# minicar_r3.net
KiCad netlist of a schematic drawn in EAGLE
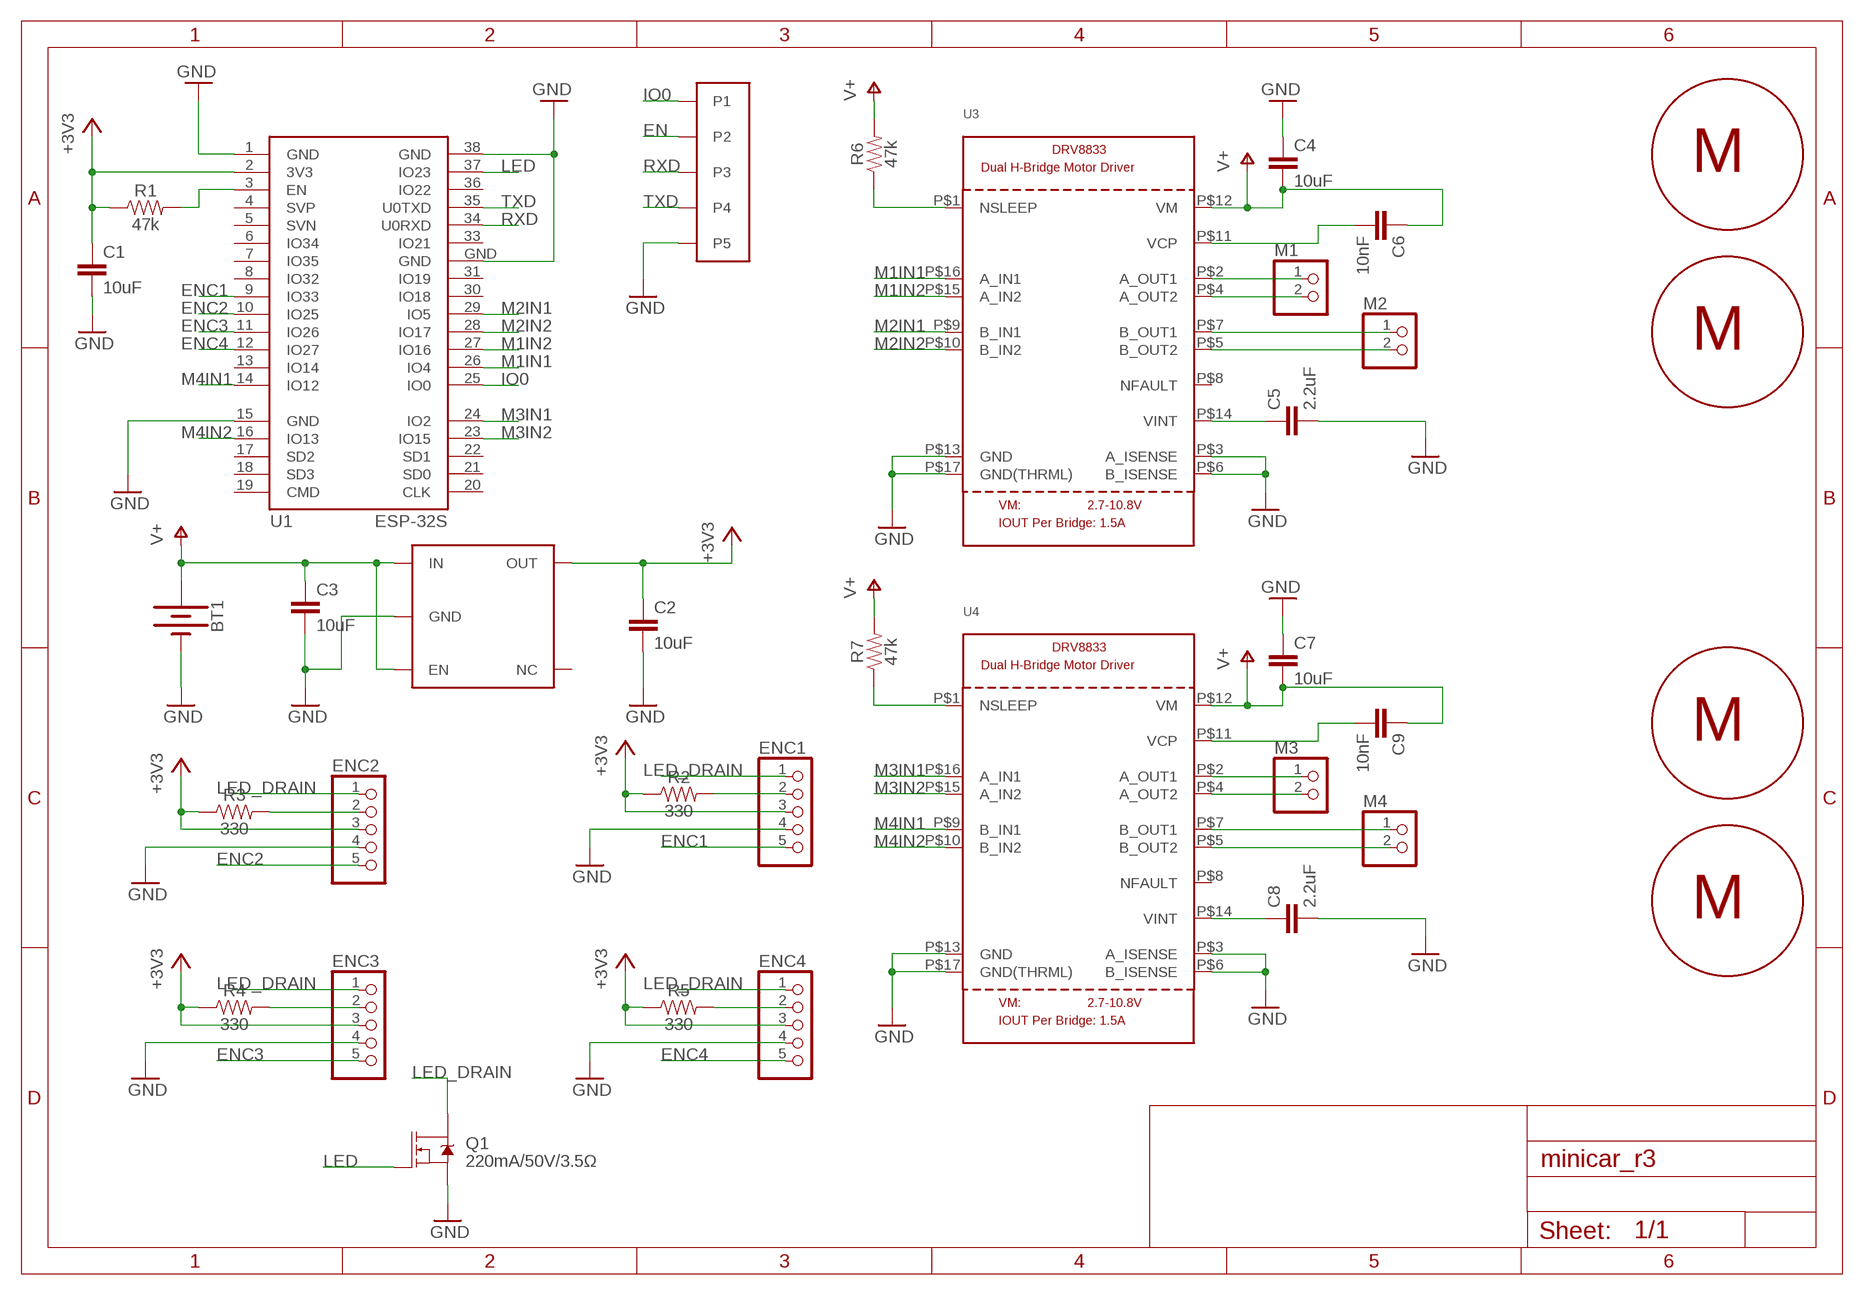
[diagram p0: schematic, sheet 1]

(export (version "E")
  (design (tool "Eeschema 10.0.6"))
  (components
    (comp (ref "BT1")
      (value "BATTERY-AA")
      (footprint "eagle-import:BATTERY-AA")
      (libsource (lib "eagle-import") (part "BATTERY-AA"))
    )
    (comp (ref "C1")
      (value "10uF")
      (footprint "eagle-import:0805")
      (libsource (lib "eagle-import") (part "10UF-0805-10V-10%"))
    )
    (comp (ref "C2")
      (value "10uF")
      (footprint "eagle-import:0805")
      (libsource (lib "eagle-import") (part "10UF-0805-10V-10%"))
    )
    (comp (ref "C3")
      (value "10uF")
      (footprint "eagle-import:0805")
      (libsource (lib "eagle-import") (part "10UF-0805-10V-10%"))
    )
    (comp (ref "C4")
      (value "10uF")
      (footprint "eagle-import:0805")
      (libsource (lib "eagle-import") (part "10UF-0805-10V-10%"))
    )
    (comp (ref "C5")
      (value "2.2uF")
      (footprint "eagle-import:0603")
      (libsource (lib "eagle-import") (part "2.2UF-0603-10V-20%"))
    )
    (comp (ref "C6")
      (value "10nF")
      (footprint "eagle-import:0603")
      (libsource (lib "eagle-import") (part "10NF-0603-50V-10%"))
    )
    (comp (ref "C7")
      (value "10uF")
      (footprint "eagle-import:0805")
      (libsource (lib "eagle-import") (part "10UF-0805-10V-10%"))
    )
    (comp (ref "C8")
      (value "2.2uF")
      (footprint "eagle-import:0603")
      (libsource (lib "eagle-import") (part "2.2UF-0603-10V-20%"))
    )
    (comp (ref "C9")
      (value "10nF")
      (footprint "eagle-import:0603")
      (libsource (lib "eagle-import") (part "10NF-0603-50V-10%"))
    )
    (comp (ref "ENC1")
      (value "PINHD-1X5")
      (footprint "eagle-import:1X05")
      (libsource (lib "eagle-import") (part "PINHD-1X5"))
    )
    (comp (ref "ENC2")
      (value "PINHD-1X5")
      (footprint "eagle-import:1X05")
      (libsource (lib "eagle-import") (part "PINHD-1X5"))
    )
    (comp (ref "ENC3")
      (value "PINHD-1X5")
      (footprint "eagle-import:1X05")
      (libsource (lib "eagle-import") (part "PINHD-1X5"))
    )
    (comp (ref "ENC4")
      (value "PINHD-1X5")
      (footprint "eagle-import:1X05")
      (libsource (lib "eagle-import") (part "PINHD-1X5"))
    )
    (comp (ref "M1")
      (value "PINHD-1X2")
      (footprint "eagle-import:1X02")
      (libsource (lib "eagle-import") (part "PINHD-1X2"))
    )
    (comp (ref "M2")
      (value "PINHD-1X2")
      (footprint "eagle-import:1X02")
      (libsource (lib "eagle-import") (part "PINHD-1X2"))
    )
    (comp (ref "M3")
      (value "PINHD-1X2")
      (footprint "eagle-import:1X02")
      (libsource (lib "eagle-import") (part "PINHD-1X2"))
    )
    (comp (ref "M4")
      (value "PINHD-1X2")
      (footprint "eagle-import:1X02")
      (libsource (lib "eagle-import") (part "PINHD-1X2"))
    )
    (comp (ref "Q1")
      (value "220mA/50V/3.5Ω")
      (footprint "eagle-import:SOT23-3")
      (libsource (lib "eagle-import") (part "MOSFET-NCH-BSS138"))
    )
    (comp (ref "R1")
      (value "47k")
      (footprint "eagle-import:0603")
      (libsource (lib "eagle-import") (part "47KOHM-0603-1/10W-1%"))
    )
    (comp (ref "R2")
      (value "330")
      (footprint "eagle-import:0603")
      (libsource (lib "eagle-import") (part "330OHM-0603-1/10W-1%"))
    )
    (comp (ref "R3")
      (value "330")
      (footprint "eagle-import:0603")
      (libsource (lib "eagle-import") (part "330OHM-0603-1/10W-1%"))
    )
    (comp (ref "R4")
      (value "330")
      (footprint "eagle-import:0603")
      (libsource (lib "eagle-import") (part "330OHM-0603-1/10W-1%"))
    )
    (comp (ref "R5")
      (value "330")
      (footprint "eagle-import:0603")
      (libsource (lib "eagle-import") (part "330OHM-0603-1/10W-1%"))
    )
    (comp (ref "R6")
      (value "47k")
      (footprint "eagle-import:0603")
      (libsource (lib "eagle-import") (part "47KOHM-0603-1/10W-1%"))
    )
    (comp (ref "R7")
      (value "47k")
      (footprint "eagle-import:0603")
      (libsource (lib "eagle-import") (part "47KOHM-0603-1/10W-1%"))
    )
    (comp (ref "U$2")
      (value "MOTOR_10X27MM")
      (footprint "eagle-import:MOTOR")
      (libsource (lib "eagle-import") (part "MOTOR_10X27MM"))
    )
    (comp (ref "U$3")
      (value "MOTOR_10X27MM")
      (footprint "eagle-import:MOTOR")
      (libsource (lib "eagle-import") (part "MOTOR_10X27MM"))
    )
    (comp (ref "U$4")
      (value "MOTOR_10X27MM")
      (footprint "eagle-import:MOTOR")
      (libsource (lib "eagle-import") (part "MOTOR_10X27MM"))
    )
    (comp (ref "U$5")
      (value "MOTOR_10X27MM")
      (footprint "eagle-import:MOTOR")
      (libsource (lib "eagle-import") (part "MOTOR_10X27MM"))
    )
    (comp (ref "U1")
      (value "ESP-32S")
      (footprint "eagle-import:ESP-32S")
      (libsource (lib "eagle-import") (part "ESP-32S"))
    )
    (comp (ref "U2")
      (value "53047")
      (footprint "eagle-import:PICOBLADE_53047")
      (libsource (lib "eagle-import") (part "53047"))
    )
    (comp (ref "U3")
      (value "DRV8833")
      (footprint "eagle-import:HTSSOP16")
      (libsource (lib "eagle-import") (part "DRV8833"))
    )
    (comp (ref "U4")
      (value "DRV8833")
      (footprint "eagle-import:HTSSOP16")
      (libsource (lib "eagle-import") (part "DRV8833"))
    )
    (comp (ref "U5")
      (value "TLV755")
      (footprint "eagle-import:SOT23-DBV")
      (libsource (lib "eagle-import") (part "TLV755"))
    )
  )
  (nets
    (net (code "1") (name "+3V3") (class "Default")
      (node (ref "C1") (pin "1") (pinfunction "1_1") (pintype "passive"))
      (node (ref "C2") (pin "1") (pinfunction "1_1") (pintype "passive"))
      (node (ref "ENC1") (pin "3") (pinfunction "3_3") (pintype "passive"))
      (node (ref "ENC2") (pin "3") (pinfunction "3_3") (pintype "passive"))
      (node (ref "ENC3") (pin "3") (pinfunction "3_3") (pintype "passive"))
      (node (ref "ENC4") (pin "3") (pinfunction "3_3") (pintype "passive"))
      (node (ref "R1") (pin "1") (pinfunction "1_1") (pintype "passive"))
      (node (ref "R2") (pin "1") (pinfunction "1_1") (pintype "passive"))
      (node (ref "R3") (pin "1") (pinfunction "1_1") (pintype "passive"))
      (node (ref "R4") (pin "1") (pinfunction "1_1") (pintype "passive"))
      (node (ref "R5") (pin "1") (pinfunction "1_1") (pintype "passive"))
      (node (ref "U1") (pin "2") (pinfunction "3V3_2") (pintype "power_in"))
      (node (ref "U5") (pin "5") (pinfunction "OUT_5") (pintype "bidirectional"))
    )
    (net (code "2") (name "/EN") (class "Default")
      (node (ref "R1") (pin "2") (pinfunction "2_2") (pintype "passive"))
      (node (ref "U1") (pin "3") (pinfunction "EN_3") (pintype "input"))
      (node (ref "U2") (pin "P$2") (pinfunction "P2_P$2") (pintype "bidirectional"))
    )
    (net (code "3") (name "/ENC1") (class "Default")
      (node (ref "ENC1") (pin "5") (pinfunction "5_5") (pintype "passive"))
      (node (ref "U1") (pin "9") (pinfunction "IO33_9") (pintype "bidirectional"))
    )
    (net (code "4") (name "/ENC2") (class "Default")
      (node (ref "ENC2") (pin "5") (pinfunction "5_5") (pintype "passive"))
      (node (ref "U1") (pin "10") (pinfunction "IO25_10") (pintype "bidirectional"))
    )
    (net (code "5") (name "/ENC3") (class "Default")
      (node (ref "ENC3") (pin "5") (pinfunction "5_5") (pintype "passive"))
      (node (ref "U1") (pin "11") (pinfunction "IO26_11") (pintype "bidirectional"))
    )
    (net (code "6") (name "/ENC4") (class "Default")
      (node (ref "ENC4") (pin "5") (pinfunction "5_5") (pintype "passive"))
      (node (ref "U1") (pin "12") (pinfunction "IO27_12") (pintype "bidirectional"))
    )
    (net (code "7") (name "/IO0") (class "Default")
      (node (ref "U1") (pin "25") (pinfunction "IO0_25") (pintype "bidirectional"))
      (node (ref "U2") (pin "P$1") (pinfunction "P1_P$1") (pintype "bidirectional"))
    )
    (net (code "8") (name "/LED") (class "Default")
      (node (ref "Q1") (pin "1") (pinfunction "G_1") (pintype "bidirectional"))
      (node (ref "U1") (pin "37") (pinfunction "IO23_37") (pintype "bidirectional"))
    )
    (net (code "9") (name "/LED_DRAIN") (class "Default")
      (node (ref "ENC1") (pin "1") (pinfunction "1_1") (pintype "passive"))
      (node (ref "ENC2") (pin "1") (pinfunction "1_1") (pintype "passive"))
      (node (ref "ENC3") (pin "1") (pinfunction "1_1") (pintype "passive"))
      (node (ref "ENC4") (pin "1") (pinfunction "1_1") (pintype "passive"))
      (node (ref "Q1") (pin "3") (pinfunction "D_3") (pintype "bidirectional"))
    )
    (net (code "10") (name "/M1IN1") (class "Default")
      (node (ref "U1") (pin "26") (pinfunction "IO4_26") (pintype "bidirectional"))
      (node (ref "U3") (pin "P$16") (pinfunction "A_IN1_P$16") (pintype "input"))
    )
    (net (code "11") (name "/M1IN2") (class "Default")
      (node (ref "U1") (pin "27") (pinfunction "IO16_27") (pintype "bidirectional"))
      (node (ref "U3") (pin "P$15") (pinfunction "A_IN2_P$15") (pintype "input"))
    )
    (net (code "12") (name "/M2IN1") (class "Default")
      (node (ref "U1") (pin "29") (pinfunction "IO5_29") (pintype "bidirectional"))
      (node (ref "U3") (pin "P$9") (pinfunction "B_IN1_P$9") (pintype "input"))
    )
    (net (code "13") (name "/M2IN2") (class "Default")
      (node (ref "U1") (pin "28") (pinfunction "IO17_28") (pintype "bidirectional"))
      (node (ref "U3") (pin "P$10") (pinfunction "B_IN2_P$10") (pintype "input"))
    )
    (net (code "14") (name "/M3IN1") (class "Default")
      (node (ref "U1") (pin "24") (pinfunction "IO2_24") (pintype "bidirectional"))
      (node (ref "U4") (pin "P$16") (pinfunction "A_IN1_P$16") (pintype "input"))
    )
    (net (code "15") (name "/M3IN2") (class "Default")
      (node (ref "U1") (pin "23") (pinfunction "IO15_23") (pintype "bidirectional"))
      (node (ref "U4") (pin "P$15") (pinfunction "A_IN2_P$15") (pintype "input"))
    )
    (net (code "16") (name "/M4IN1") (class "Default")
      (node (ref "U1") (pin "14") (pinfunction "IO12_14") (pintype "bidirectional"))
      (node (ref "U4") (pin "P$9") (pinfunction "B_IN1_P$9") (pintype "input"))
    )
    (net (code "17") (name "/M4IN2") (class "Default")
      (node (ref "U1") (pin "16") (pinfunction "IO13_16") (pintype "bidirectional"))
      (node (ref "U4") (pin "P$10") (pinfunction "B_IN2_P$10") (pintype "input"))
    )
    (net (code "18") (name "/RXD") (class "Default")
      (node (ref "U1") (pin "34") (pinfunction "U0RXD_34") (pintype "bidirectional"))
      (node (ref "U2") (pin "P$3") (pinfunction "P3_P$3") (pintype "bidirectional"))
    )
    (net (code "19") (name "/TXD") (class "Default")
      (node (ref "U1") (pin "35") (pinfunction "U0TXD_35") (pintype "bidirectional"))
      (node (ref "U2") (pin "P$4") (pinfunction "P4_P$4") (pintype "bidirectional"))
    )
    (net (code "20") (name "GND") (class "Default")
      (node (ref "BT1") (pin "GND@1") (pinfunction "-_GND@1") (pintype "power_in"))
      (node (ref "C1") (pin "2") (pinfunction "2_2") (pintype "passive"))
      (node (ref "C2") (pin "2") (pinfunction "2_2") (pintype "passive"))
      (node (ref "C3") (pin "2") (pinfunction "2_2") (pintype "passive"))
      (node (ref "C4") (pin "1") (pinfunction "1_1") (pintype "passive"))
      (node (ref "C5") (pin "2") (pinfunction "2_2") (pintype "passive"))
      (node (ref "C7") (pin "1") (pinfunction "1_1") (pintype "passive"))
      (node (ref "C8") (pin "2") (pinfunction "2_2") (pintype "passive"))
      (node (ref "ENC1") (pin "4") (pinfunction "4_4") (pintype "passive"))
      (node (ref "ENC2") (pin "4") (pinfunction "4_4") (pintype "passive"))
      (node (ref "ENC3") (pin "4") (pinfunction "4_4") (pintype "passive"))
      (node (ref "ENC4") (pin "4") (pinfunction "4_4") (pintype "passive"))
      (node (ref "Q1") (pin "2") (pinfunction "S_2") (pintype "bidirectional"))
      (node (ref "U1") (pin "1") (pinfunction "GND_1") (pintype "power_in"))
      (node (ref "U1") (pin "15") (pinfunction "GND_15") (pintype "power_in"))
      (node (ref "U1") (pin "38") (pinfunction "GND_38") (pintype "power_in"))
      (node (ref "U1") (pin "GND") (pinfunction "GND_GND") (pintype "power_in"))
      (node (ref "U2") (pin "P$5") (pinfunction "P5_P$5") (pintype "bidirectional"))
      (node (ref "U3") (pin "P$13") (pinfunction "GND_P$13") (pintype "power_in"))
      (node (ref "U3") (pin "P$17") (pinfunction "GND(THRML)_P$17") (pintype "power_in"))
      (node (ref "U3") (pin "P$3") (pinfunction "A_ISENSE_P$3") (pintype "bidirectional"))
      (node (ref "U3") (pin "P$6") (pinfunction "B_ISENSE_P$6") (pintype "bidirectional"))
      (node (ref "U4") (pin "P$13") (pinfunction "GND_P$13") (pintype "power_in"))
      (node (ref "U4") (pin "P$17") (pinfunction "GND(THRML)_P$17") (pintype "power_in"))
      (node (ref "U4") (pin "P$3") (pinfunction "A_ISENSE_P$3") (pintype "bidirectional"))
      (node (ref "U4") (pin "P$6") (pinfunction "B_ISENSE_P$6") (pintype "bidirectional"))
      (node (ref "U5") (pin "2") (pinfunction "GND_2") (pintype "bidirectional"))
    )
    (net (code "21") (name "Net-(ENC1-Pad2)") (class "Default")
      (node (ref "ENC1") (pin "2") (pinfunction "2_2") (pintype "passive"))
      (node (ref "R2") (pin "2") (pinfunction "2_2") (pintype "passive"))
    )
    (net (code "22") (name "Net-(ENC2-Pad2)") (class "Default")
      (node (ref "ENC2") (pin "2") (pinfunction "2_2") (pintype "passive"))
      (node (ref "R3") (pin "2") (pinfunction "2_2") (pintype "passive"))
    )
    (net (code "23") (name "Net-(ENC3-Pad2)") (class "Default")
      (node (ref "ENC3") (pin "2") (pinfunction "2_2") (pintype "passive"))
      (node (ref "R4") (pin "2") (pinfunction "2_2") (pintype "passive"))
    )
    (net (code "24") (name "Net-(ENC4-Pad2)") (class "Default")
      (node (ref "ENC4") (pin "2") (pinfunction "2_2") (pintype "passive"))
      (node (ref "R5") (pin "2") (pinfunction "2_2") (pintype "passive"))
    )
    (net (code "25") (name "Net-(U3-A_OUT1)") (class "Default")
      (node (ref "M1") (pin "1") (pinfunction "1_1") (pintype "passive"))
      (node (ref "U3") (pin "P$2") (pinfunction "A_OUT1_P$2") (pintype "output"))
    )
    (net (code "26") (name "Net-(U3-A_OUT2)") (class "Default")
      (node (ref "M1") (pin "2") (pinfunction "2_2") (pintype "passive"))
      (node (ref "U3") (pin "P$4") (pinfunction "A_OUT2_P$4") (pintype "output"))
    )
    (net (code "27") (name "Net-(U3-B_OUT1)") (class "Default")
      (node (ref "M2") (pin "1") (pinfunction "1_1") (pintype "passive"))
      (node (ref "U3") (pin "P$7") (pinfunction "B_OUT1_P$7") (pintype "output"))
    )
    (net (code "28") (name "Net-(U3-B_OUT2)") (class "Default")
      (node (ref "M2") (pin "2") (pinfunction "2_2") (pintype "passive"))
      (node (ref "U3") (pin "P$5") (pinfunction "B_OUT2_P$5") (pintype "output"))
    )
    (net (code "29") (name "Net-(U3-NSLEEP)") (class "Default")
      (node (ref "R6") (pin "1") (pinfunction "1_1") (pintype "passive"))
      (node (ref "U3") (pin "P$1") (pinfunction "NSLEEP_P$1") (pintype "input"))
    )
    (net (code "30") (name "Net-(U3-VCP)") (class "Default")
      (node (ref "C6") (pin "2") (pinfunction "2_2") (pintype "passive"))
      (node (ref "U3") (pin "P$11") (pinfunction "VCP_P$11") (pintype "bidirectional"))
    )
    (net (code "31") (name "Net-(U3-VINT)") (class "Default")
      (node (ref "C5") (pin "1") (pinfunction "1_1") (pintype "passive"))
      (node (ref "U3") (pin "P$14") (pinfunction "VINT_P$14") (pintype "power_in"))
    )
    (net (code "32") (name "Net-(U4-A_OUT1)") (class "Default")
      (node (ref "M3") (pin "1") (pinfunction "1_1") (pintype "passive"))
      (node (ref "U4") (pin "P$2") (pinfunction "A_OUT1_P$2") (pintype "output"))
    )
    (net (code "33") (name "Net-(U4-A_OUT2)") (class "Default")
      (node (ref "M3") (pin "2") (pinfunction "2_2") (pintype "passive"))
      (node (ref "U4") (pin "P$4") (pinfunction "A_OUT2_P$4") (pintype "output"))
    )
    (net (code "34") (name "Net-(U4-B_OUT1)") (class "Default")
      (node (ref "M4") (pin "1") (pinfunction "1_1") (pintype "passive"))
      (node (ref "U4") (pin "P$7") (pinfunction "B_OUT1_P$7") (pintype "output"))
    )
    (net (code "35") (name "Net-(U4-B_OUT2)") (class "Default")
      (node (ref "M4") (pin "2") (pinfunction "2_2") (pintype "passive"))
      (node (ref "U4") (pin "P$5") (pinfunction "B_OUT2_P$5") (pintype "output"))
    )
    (net (code "36") (name "Net-(U4-NSLEEP)") (class "Default")
      (node (ref "R7") (pin "1") (pinfunction "1_1") (pintype "passive"))
      (node (ref "U4") (pin "P$1") (pinfunction "NSLEEP_P$1") (pintype "input"))
    )
    (net (code "37") (name "Net-(U4-VCP)") (class "Default")
      (node (ref "C9") (pin "2") (pinfunction "2_2") (pintype "passive"))
      (node (ref "U4") (pin "P$11") (pinfunction "VCP_P$11") (pintype "bidirectional"))
    )
    (net (code "38") (name "Net-(U4-VINT)") (class "Default")
      (node (ref "C8") (pin "1") (pinfunction "1_1") (pintype "passive"))
      (node (ref "U4") (pin "P$14") (pinfunction "VINT_P$14") (pintype "power_in"))
    )
    (net (code "39") (name "V+") (class "Default")
      (node (ref "BT1") (pin "PWR@1") (pinfunction "+_PWR@1") (pintype "power_in"))
      (node (ref "C3") (pin "1") (pinfunction "1_1") (pintype "passive"))
      (node (ref "C4") (pin "2") (pinfunction "2_2") (pintype "passive"))
      (node (ref "C6") (pin "1") (pinfunction "1_1") (pintype "passive"))
      (node (ref "C7") (pin "2") (pinfunction "2_2") (pintype "passive"))
      (node (ref "C9") (pin "1") (pinfunction "1_1") (pintype "passive"))
      (node (ref "R6") (pin "2") (pinfunction "2_2") (pintype "passive"))
      (node (ref "R7") (pin "2") (pinfunction "2_2") (pintype "passive"))
      (node (ref "U3") (pin "P$12") (pinfunction "VM_P$12") (pintype "power_in"))
      (node (ref "U4") (pin "P$12") (pinfunction "VM_P$12") (pintype "power_in"))
      (node (ref "U5") (pin "1") (pinfunction "IN_1") (pintype "bidirectional"))
      (node (ref "U5") (pin "3") (pinfunction "EN_3") (pintype "bidirectional"))
    )
    (net (code "40") (name "unconnected-(U1-CLK-Pad20)") (class "Default")
      (node (ref "U1") (pin "20") (pinfunction "CLK_20") (pintype "bidirectional"))
    )
    (net (code "41") (name "unconnected-(U1-CMD-Pad19)") (class "Default")
      (node (ref "U1") (pin "19") (pinfunction "CMD_19") (pintype "bidirectional"))
    )
    (net (code "42") (name "unconnected-(U1-IO14-Pad13)") (class "Default")
      (node (ref "U1") (pin "13") (pinfunction "IO14_13") (pintype "bidirectional"))
    )
    (net (code "43") (name "unconnected-(U1-IO18-Pad30)") (class "Default")
      (node (ref "U1") (pin "30") (pinfunction "IO18_30") (pintype "bidirectional"))
    )
    (net (code "44") (name "unconnected-(U1-IO19-Pad31)") (class "Default")
      (node (ref "U1") (pin "31") (pinfunction "IO19_31") (pintype "bidirectional"))
    )
    (net (code "45") (name "unconnected-(U1-IO21-Pad33)") (class "Default")
      (node (ref "U1") (pin "33") (pinfunction "IO21_33") (pintype "bidirectional"))
    )
    (net (code "46") (name "unconnected-(U1-IO22-Pad36)") (class "Default")
      (node (ref "U1") (pin "36") (pinfunction "IO22_36") (pintype "bidirectional"))
    )
    (net (code "47") (name "unconnected-(U1-IO32-Pad8)") (class "Default")
      (node (ref "U1") (pin "8") (pinfunction "IO32_8") (pintype "bidirectional"))
    )
    (net (code "48") (name "unconnected-(U1-IO34-Pad6)") (class "Default")
      (node (ref "U1") (pin "6") (pinfunction "IO34_6") (pintype "bidirectional"))
    )
    (net (code "49") (name "unconnected-(U1-IO35-Pad7)") (class "Default")
      (node (ref "U1") (pin "7") (pinfunction "IO35_7") (pintype "bidirectional"))
    )
    (net (code "50") (name "unconnected-(U1-SD0-Pad21)") (class "Default")
      (node (ref "U1") (pin "21") (pinfunction "SD0_21") (pintype "bidirectional"))
    )
    (net (code "51") (name "unconnected-(U1-SD1-Pad22)") (class "Default")
      (node (ref "U1") (pin "22") (pinfunction "SD1_22") (pintype "bidirectional"))
    )
    (net (code "52") (name "unconnected-(U1-SD2-Pad17)") (class "Default")
      (node (ref "U1") (pin "17") (pinfunction "SD2_17") (pintype "bidirectional"))
    )
    (net (code "53") (name "unconnected-(U1-SD3-Pad18)") (class "Default")
      (node (ref "U1") (pin "18") (pinfunction "SD3_18") (pintype "bidirectional"))
    )
    (net (code "54") (name "unconnected-(U1-SVN-Pad5)") (class "Default")
      (node (ref "U1") (pin "5") (pinfunction "SVN_5") (pintype "bidirectional"))
    )
    (net (code "55") (name "unconnected-(U1-SVP-Pad4)") (class "Default")
      (node (ref "U1") (pin "4") (pinfunction "SVP_4") (pintype "bidirectional"))
    )
    (net (code "56") (name "unconnected-(U3-NFAULT-PadP$8)") (class "Default")
      (node (ref "U3") (pin "P$8") (pinfunction "NFAULT_P$8") (pintype "bidirectional"))
    )
    (net (code "57") (name "unconnected-(U4-NFAULT-PadP$8)") (class "Default")
      (node (ref "U4") (pin "P$8") (pinfunction "NFAULT_P$8") (pintype "bidirectional"))
    )
    (net (code "58") (name "unconnected-(U5-NC-Pad4)") (class "Default")
      (node (ref "U5") (pin "4") (pinfunction "NC_4") (pintype "bidirectional"))
    )
  )
)
